# SensorStick.net
KiCad netlist of a schematic drawn in EAGLE
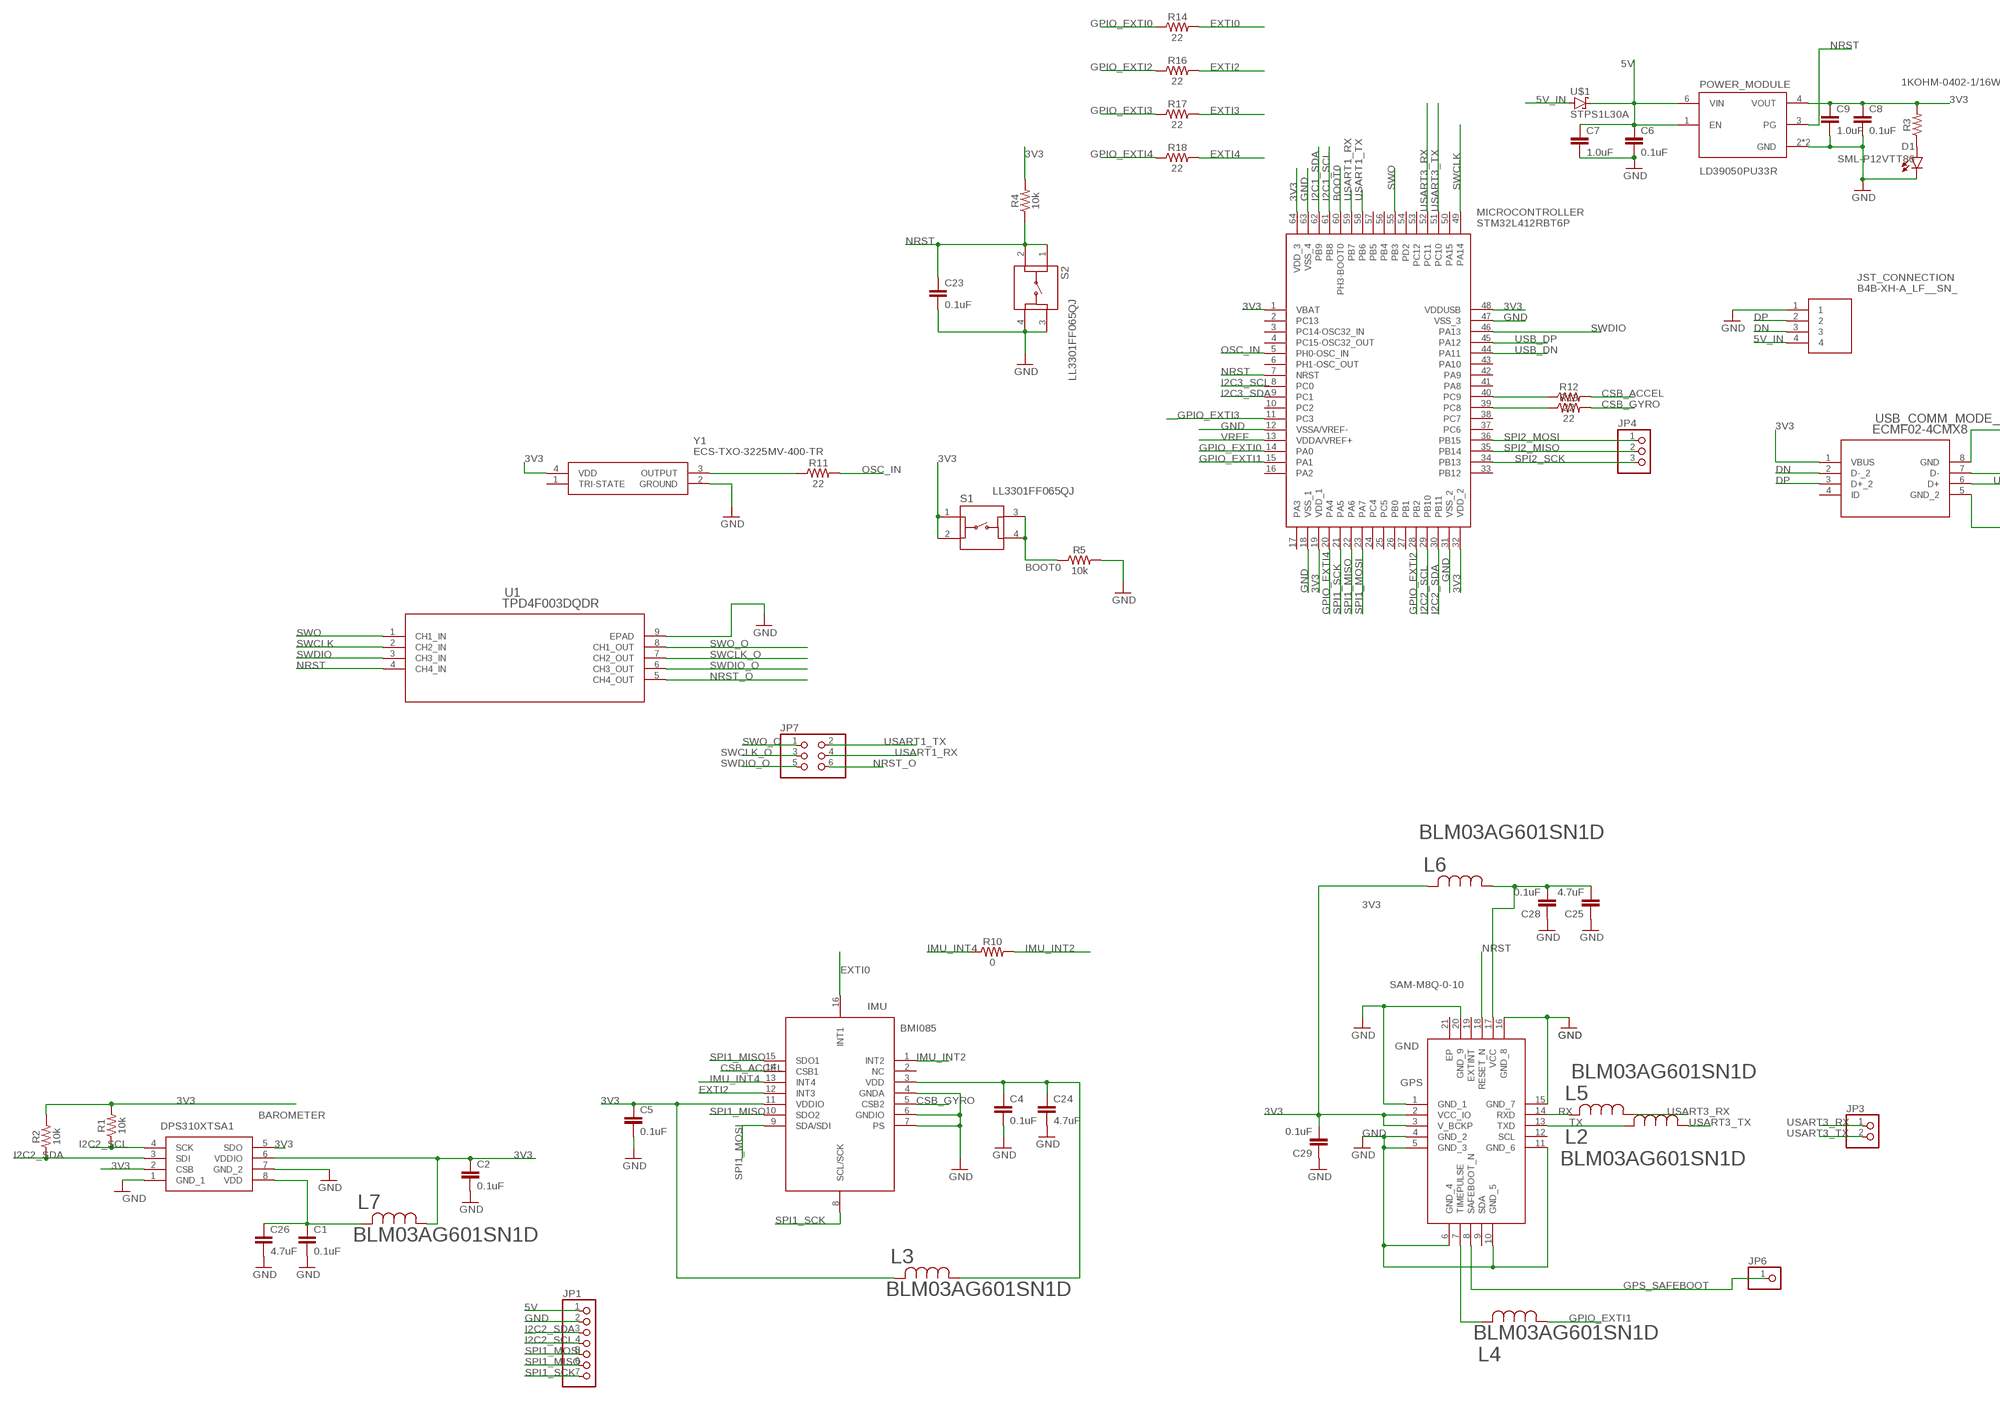
[diagram p0: schematic, sheet 1, part 1 of 2]
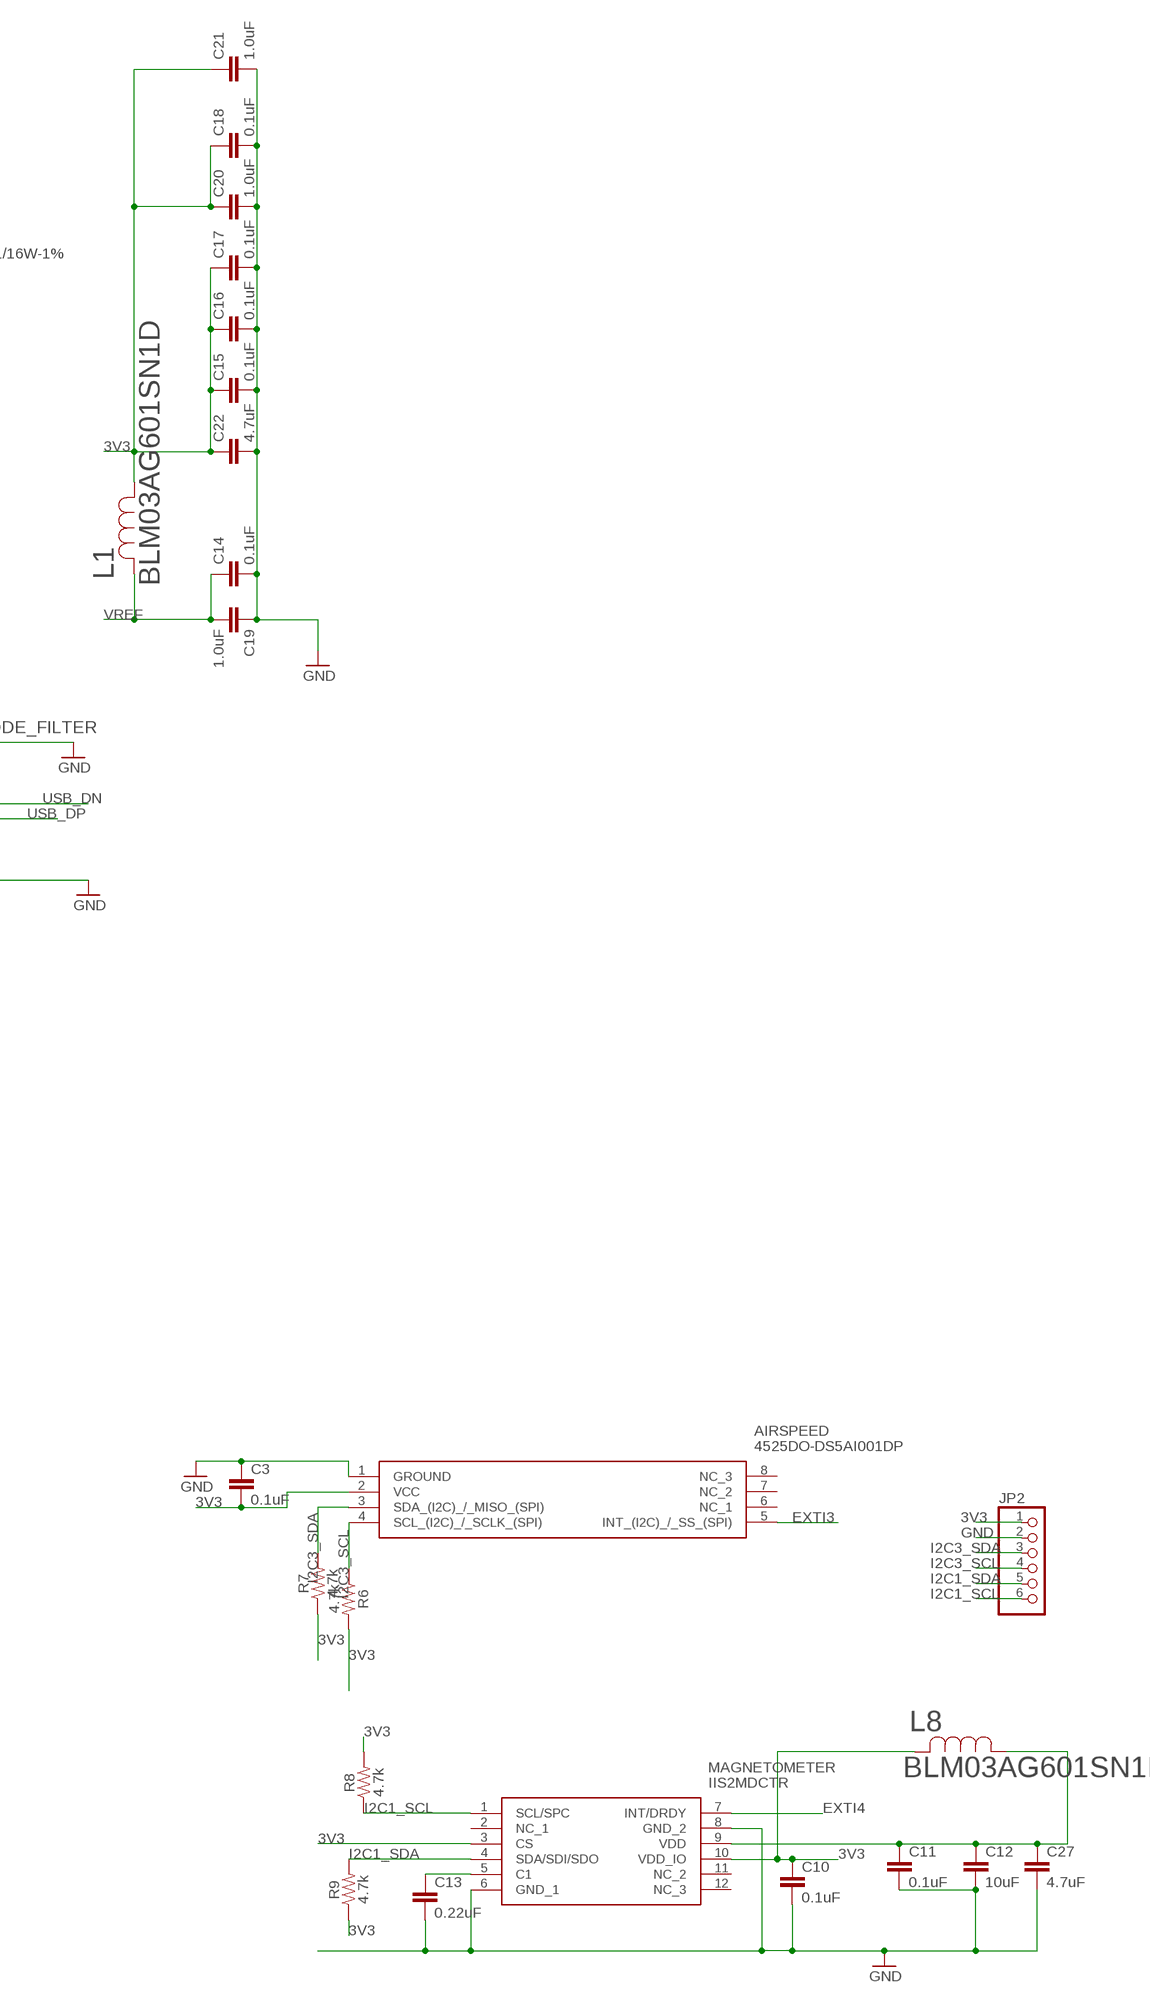
[diagram p1: schematic, sheet 1, part 2 of 2]

(export (version "E")
  (design (tool "Eeschema 10.0.6"))
  (components
    (comp (ref "AIRSPEED")
      (value "4525DO-DS5AI001DP")
      (footprint "eagle-import:4525DO-DS...P")
      (fields (field (name "MOUSER_PART_NUMBER") "824-4525DODS5AI001DP"))
      (libsource (lib "eagle-import") (part "4525DO-DS5AI001DP"))
    )
    (comp (ref "BAROMETER")
      (value "DPS310XTSA1")
      (footprint "eagle-import:DPS310XTSA1")
      (fields (field (name "MOUSER_PART_NUMBER") "726-DPS310XTSA1"))
      (libsource (lib "eagle-import") (part "DPS310XTSA1"))
    )
    (comp (ref "C1")
      (value "0.1uF")
      (footprint "eagle-import:0402")
      (libsource (lib "eagle-import") (part "0.1UF-0402-6.3V-10%-X7R"))
    )
    (comp (ref "C2")
      (value "0.1uF")
      (footprint "eagle-import:0402")
      (libsource (lib "eagle-import") (part "0.1UF-0402-6.3V-10%-X7R"))
    )
    (comp (ref "C3")
      (value "0.1uF")
      (footprint "eagle-import:0402")
      (fields (field (name "SPICEPREFIX") "C"))
      (libsource (lib "eagle-import") (part "0.1UF-0402-6.3V-10%-X7R"))
    )
    (comp (ref "C4")
      (value "0.1uF")
      (footprint "eagle-import:0402")
      (libsource (lib "eagle-import") (part "0.1UF-0402-6.3V-10%-X7R"))
    )
    (comp (ref "C5")
      (value "0.1uF")
      (footprint "eagle-import:0402")
      (libsource (lib "eagle-import") (part "0.1UF-0402-6.3V-10%-X7R"))
    )
    (comp (ref "C6")
      (value "0.1uF")
      (footprint "eagle-import:0402")
      (libsource (lib "eagle-import") (part "0.1UF-0402-6.3V-10%-X7R"))
    )
    (comp (ref "C7")
      (value "1.0uF")
      (footprint "eagle-import:0402")
      (libsource (lib "eagle-import") (part "1.0UF-0402-16V-10%"))
    )
    (comp (ref "C8")
      (value "0.1uF")
      (footprint "eagle-import:0402")
      (libsource (lib "eagle-import") (part "0.1UF-0402-6.3V-10%-X7R"))
    )
    (comp (ref "C9")
      (value "1.0uF")
      (footprint "eagle-import:0402")
      (libsource (lib "eagle-import") (part "1.0UF-0402-16V-10%"))
    )
    (comp (ref "C10")
      (value "0.1uF")
      (footprint "eagle-import:0402")
      (libsource (lib "eagle-import") (part "0.1UF-0402-6.3V-10%-X7R"))
    )
    (comp (ref "C11")
      (value "0.1uF")
      (footprint "eagle-import:0402")
      (libsource (lib "eagle-import") (part "0.1UF-0402-6.3V-10%-X7R"))
    )
    (comp (ref "C12")
      (value "10uF")
      (footprint "eagle-import:0603")
      (libsource (lib "eagle-import") (part "10UF-0603-6.3V-20%"))
    )
    (comp (ref "C13")
      (value "0.22uF")
      (footprint "eagle-import:0603")
      (libsource (lib "eagle-import") (part "0.22UF-0603-25V-10%"))
    )
    (comp (ref "C14")
      (value "0.1uF")
      (footprint "eagle-import:0603")
      (libsource (lib "eagle-import") (part "SparkFun-Capacitors_510_0.1UF-0603-25V-5%"))
    )
    (comp (ref "C15")
      (value "0.1uF")
      (footprint "eagle-import:0603")
      (libsource (lib "eagle-import") (part "SparkFun-Capacitors_510_0.1UF-0603-25V-5%"))
    )
    (comp (ref "C16")
      (value "0.1uF")
      (footprint "eagle-import:0603")
      (libsource (lib "eagle-import") (part "SparkFun-Capacitors_510_0.1UF-0603-25V-5%"))
    )
    (comp (ref "C17")
      (value "0.1uF")
      (footprint "eagle-import:0603")
      (libsource (lib "eagle-import") (part "SparkFun-Capacitors_510_0.1UF-0603-25V-5%"))
    )
    (comp (ref "C18")
      (value "0.1uF")
      (footprint "eagle-import:0603")
      (libsource (lib "eagle-import") (part "SparkFun-Capacitors_510_0.1UF-0603-25V-5%"))
    )
    (comp (ref "C19")
      (value "1.0uF")
      (footprint "eagle-import:0805")
      (libsource (lib "eagle-import") (part "SparkFun-Capacitors_510_1.0UF-0805-25V-10%"))
    )
    (comp (ref "C20")
      (value "1.0uF")
      (footprint "eagle-import:0805")
      (libsource (lib "eagle-import") (part "SparkFun-Capacitors_510_1.0UF-0805-25V-10%"))
    )
    (comp (ref "C21")
      (value "1.0uF")
      (footprint "eagle-import:0805")
      (libsource (lib "eagle-import") (part "SparkFun-Capacitors_510_1.0UF-0805-25V-10%"))
    )
    (comp (ref "C22")
      (value "4.7uF")
      (footprint "eagle-import:0603")
      (libsource (lib "eagle-import") (part "4.7UF0603"))
    )
    (comp (ref "C23")
      (value "0.1uF")
      (footprint "eagle-import:0603")
      (libsource (lib "eagle-import") (part "SparkFun-Capacitors_510_0.1UF-0603-25V-5%"))
    )
    (comp (ref "C24")
      (value "4.7uF")
      (footprint "eagle-import:0603")
      (libsource (lib "eagle-import") (part "4.7UF0603"))
    )
    (comp (ref "C25")
      (value "4.7uF")
      (footprint "eagle-import:0603")
      (libsource (lib "eagle-import") (part "4.7UF0603"))
    )
    (comp (ref "C26")
      (value "4.7uF")
      (footprint "eagle-import:0603")
      (libsource (lib "eagle-import") (part "4.7UF0603"))
    )
    (comp (ref "C27")
      (value "4.7uF")
      (footprint "eagle-import:0603")
      (libsource (lib "eagle-import") (part "4.7UF0603"))
    )
    (comp (ref "C28")
      (value "0.1uF")
      (footprint "eagle-import:0402")
      (libsource (lib "eagle-import") (part "SparkFun-Capacitors_510_0.1UF-0402-16V-10%"))
    )
    (comp (ref "C29")
      (value "0.1uF")
      (footprint "eagle-import:0402")
      (libsource (lib "eagle-import") (part "SparkFun-Capacitors_510_0.1UF-0402-16V-10%"))
    )
    (comp (ref "D1")
      (value "SML-P12VTT86")
      (footprint "eagle-import:LED_SML-P11UTT86R")
      (fields (field (name "MF") "Rohm"))
      (libsource (lib "eagle-import") (part "SML-P12VTT86"))
    )
    (comp (ref "GPS")
      (value "SAM-M8Q-0-10")
      (footprint "eagle-import:SAMM8Q010")
      (libsource (lib "eagle-import") (part "SAM-M8Q-0-10"))
    )
    (comp (ref "IMU")
      (value "BMI085")
      (footprint "eagle-import:BMI085")
      (fields (field (name "MOUSER_PART_NUMBER") "262-BMI085"))
      (libsource (lib "eagle-import") (part "BMI085"))
    )
    (comp (ref "JP1")
      (value "PINHD-1X7")
      (footprint "eagle-import:1X07")
      (libsource (lib "eagle-import") (part "PINHD-1X7"))
    )
    (comp (ref "JP2")
      (value "PINHD-1X6")
      (footprint "eagle-import:1X06")
      (libsource (lib "eagle-import") (part "PINHD-1X6"))
    )
    (comp (ref "JP3")
      (value "PINHD-1X2")
      (footprint "eagle-import:1X02")
      (libsource (lib "eagle-import") (part "PINHD-1X2"))
    )
    (comp (ref "JP4")
      (value "PINHD-1X3")
      (footprint "eagle-import:1X03")
      (libsource (lib "eagle-import") (part "PINHD-1X3"))
    )
    (comp (ref "JP6")
      (value "PINHD-1X1")
      (footprint "eagle-import:1X01")
      (libsource (lib "eagle-import") (part "PINHD-1X1"))
    )
    (comp (ref "JP7")
      (value "PINHD-2X3")
      (footprint "eagle-import:2X03")
      (libsource (lib "eagle-import") (part "PINHD-2X3"))
    )
    (comp (ref "JST_CONNECTION")
      (value "B4B-XH-A_LF__SN_")
      (footprint "eagle-import:B4BXHALFSN")
      (fields (field (name "ARROW_PART_NUMBER") "B4B-XH-A(LF)(SN)"))
      (libsource (lib "eagle-import") (part "B4B-XH-A_LF__SN_"))
    )
    (comp (ref "L1")
      (value "BLM03AG601SN1D")
      (footprint "eagle-import:IND_BLM03_0201_MUR")
      (fields (field (name "COPYRIGHT") "Copyright (C) 2023 Ultra Librarian. All rights reserved."))
      (libsource (lib "eagle-import") (part "BLM03AG601SN1D"))
    )
    (comp (ref "L2")
      (value "BLM03AG601SN1D")
      (footprint "eagle-import:IND_BLM03_0201_MUR")
      (fields (field (name "COPYRIGHT") "Copyright (C) 2023 Ultra Librarian. All rights reserved."))
      (libsource (lib "eagle-import") (part "BLM03AG601SN1D"))
    )
    (comp (ref "L3")
      (value "BLM03AG601SN1D")
      (footprint "eagle-import:IND_BLM03_0201_MUR")
      (fields (field (name "COPYRIGHT") "Copyright (C) 2023 Ultra Librarian. All rights reserved."))
      (libsource (lib "eagle-import") (part "BLM03AG601SN1D"))
    )
    (comp (ref "L4")
      (value "BLM03AG601SN1D")
      (footprint "eagle-import:IND_BLM03_0201_MUR")
      (fields (field (name "COPYRIGHT") "Copyright (C) 2023 Ultra Librarian. All rights reserved."))
      (libsource (lib "eagle-import") (part "BLM03AG601SN1D"))
    )
    (comp (ref "L5")
      (value "BLM03AG601SN1D")
      (footprint "eagle-import:IND_BLM03_0201_MUR")
      (fields (field (name "COPYRIGHT") "Copyright (C) 2023 Ultra Librarian. All rights reserved."))
      (libsource (lib "eagle-import") (part "BLM03AG601SN1D"))
    )
    (comp (ref "L6")
      (value "BLM03AG601SN1D")
      (footprint "eagle-import:IND_BLM03_0201_MUR")
      (fields (field (name "COPYRIGHT") "Copyright (C) 2023 Ultra Librarian. All rights reserved."))
      (libsource (lib "eagle-import") (part "BLM03AG601SN1D"))
    )
    (comp (ref "L7")
      (value "BLM03AG601SN1D")
      (footprint "eagle-import:IND_BLM03_0201_MUR")
      (fields (field (name "COPYRIGHT") "Copyright (C) 2023 Ultra Librarian. All rights reserved."))
      (libsource (lib "eagle-import") (part "BLM03AG601SN1D"))
    )
    (comp (ref "L8")
      (value "BLM03AG601SN1D")
      (footprint "eagle-import:IND_BLM03_0201_MUR")
      (fields (field (name "COPYRIGHT") "Copyright (C) 2023 Ultra Librarian. All rights reserved."))
      (libsource (lib "eagle-import") (part "BLM03AG601SN1D"))
    )
    (comp (ref "MAGNETOMETER")
      (value "IIS2MDCTR")
      (footprint "eagle-import:IIS2MDCTR")
      (fields (field (name "MOUSER_PART_NUMBER") "511-IIS2MDCTR"))
      (libsource (lib "eagle-import") (part "IIS2MDCTR"))
    )
    (comp (ref "MICROCONTROLLER")
      (value "STM32L412RBT6P")
      (footprint "eagle-import:QFP50P1200X1200X160-64N")
      (fields (field (name "MOUSER_PART_NUMBER") "511-STM32L412RBT6P"))
      (libsource (lib "eagle-import") (part "STM32L412RBT6P"))
    )
    (comp (ref "POWER_MODULE")
      (value "LD39050PU33R")
      (footprint "eagle-import:SON95P300X300X100-7N")
      (fields (field (name "MF") "STMicroelectronics"))
      (libsource (lib "eagle-import") (part "LD39050PU33R"))
    )
    (comp (ref "R1")
      (value "10k")
      (footprint "eagle-import:0402")
      (libsource (lib "eagle-import") (part "10KOHM-0402-1/16W-1%"))
    )
    (comp (ref "R2")
      (value "10k")
      (footprint "eagle-import:0402")
      (libsource (lib "eagle-import") (part "10KOHM-0402-1/16W-1%"))
    )
    (comp (ref "R3")
      (value "1KOHM-0402-1/16W-1%")
      (footprint "eagle-import:0402")
      (libsource (lib "eagle-import") (part "1KOHM-0402-1/16W-1%"))
    )
    (comp (ref "R4")
      (value "10k")
      (footprint "eagle-import:0603")
      (libsource (lib "eagle-import") (part "SparkFun-Resistors_532_10KOHM-0603-1/10W-1%"))
    )
    (comp (ref "R5")
      (value "10k")
      (footprint "eagle-import:0603")
      (libsource (lib "eagle-import") (part "SparkFun-Resistors_532_10KOHM-0603-1/10W-1%"))
    )
    (comp (ref "R6")
      (value "4.7k")
      (footprint "eagle-import:0603")
      (libsource (lib "eagle-import") (part "4.7KOHM-0603-1/10W-1%"))
    )
    (comp (ref "R7")
      (value "4.7k")
      (footprint "eagle-import:0603")
      (libsource (lib "eagle-import") (part "4.7KOHM-0603-1/10W-1%"))
    )
    (comp (ref "R8")
      (value "4.7k")
      (footprint "eagle-import:0603")
      (libsource (lib "eagle-import") (part "4.7KOHM-0603-1/10W-1%"))
    )
    (comp (ref "R9")
      (value "4.7k")
      (footprint "eagle-import:0603")
      (libsource (lib "eagle-import") (part "4.7KOHM-0603-1/10W-1%"))
    )
    (comp (ref "R10")
      (value "0")
      (footprint "eagle-import:0603")
      (libsource (lib "eagle-import") (part "0OHM-0603-1/10W-5%"))
    )
    (comp (ref "R11")
      (value "22")
      (footprint "eagle-import:0402")
      (libsource (lib "eagle-import") (part "22OHM-0402-1/10W-1%"))
    )
    (comp (ref "R12")
      (value "22")
      (footprint "eagle-import:0402")
      (libsource (lib "eagle-import") (part "22OHM-0402-1/10W-1%"))
    )
    (comp (ref "R13")
      (value "22")
      (footprint "eagle-import:0402")
      (libsource (lib "eagle-import") (part "22OHM-0402-1/10W-1%"))
    )
    (comp (ref "R14")
      (value "22")
      (footprint "eagle-import:0402")
      (libsource (lib "eagle-import") (part "22OHM-0402-1/10W-1%"))
    )
    (comp (ref "R16")
      (value "22")
      (footprint "eagle-import:0402")
      (libsource (lib "eagle-import") (part "22OHM-0402-1/10W-1%"))
    )
    (comp (ref "R17")
      (value "22")
      (footprint "eagle-import:0402")
      (libsource (lib "eagle-import") (part "22OHM-0402-1/10W-1%"))
    )
    (comp (ref "R18")
      (value "22")
      (footprint "eagle-import:0402")
      (libsource (lib "eagle-import") (part "22OHM-0402-1/10W-1%"))
    )
    (comp (ref "S1")
      (value "LL3301FF065QJ")
      (footprint "eagle-import:LL3301FF065QJ")
      (fields (field (name "MOUSER_PART_NUMBER") "612-LL3301FF065QJ"))
      (libsource (lib "eagle-import") (part "LL3301FF065QJ"))
    )
    (comp (ref "S2")
      (value "LL3301FF065QJ")
      (footprint "eagle-import:LL3301FF065QJ")
      (fields (field (name "MOUSER_PART_NUMBER") "612-LL3301FF065QJ"))
      (libsource (lib "eagle-import") (part "LL3301FF065QJ"))
    )
    (comp (ref "U$1")
      (value "STPS1L30A")
      (footprint "eagle-import:DIOM5226X223N")
      (libsource (lib "eagle-import") (part "STPS1L30A"))
    )
    (comp (ref "U1")
      (value "TPD4F003DQDR")
      (footprint "eagle-import:DQD8_1P2X0P4")
      (fields (field (name "COPYRIGHT") "Copyright (C) 2023 Ultra Librarian. All rights reserved."))
      (libsource (lib "eagle-import") (part "TPD4F003DQDR"))
    )
    (comp (ref "USB_COMM_MODE_FILTER")
      (value "ECMF02-4CMX8")
      (footprint "eagle-import:MICRO_QFN-8L_STM")
      (fields (field (name "COPYRIGHT") "Copyright (C) 2023 Ultra Librarian. All rights reserved."))
      (libsource (lib "eagle-import") (part "ECMF02-4CMX8"))
    )
    (comp (ref "Y1")
      (value "ECS-TXO-3225MV-400-TR")
      (footprint "eagle-import:ECSTXO3225MV400TR")
      (libsource (lib "eagle-import") (part "ECS-TXO-3225MV-400-TR"))
    )
  )
  (nets
    (net (code "1") (name "/3V3") (class "Default")
      (node (ref "AIRSPEED") (pin "2") (pinfunction "VCC_2") (pintype "power_in"))
      (node (ref "BAROMETER") (pin "2") (pinfunction "CSB_2") (pintype "bidirectional"))
      (node (ref "BAROMETER") (pin "5") (pinfunction "SDO_5") (pintype "bidirectional"))
      (node (ref "BAROMETER") (pin "6") (pinfunction "VDDIO_6") (pintype "bidirectional"))
      (node (ref "C10") (pin "1") (pinfunction "1_1") (pintype "passive"))
      (node (ref "C15") (pin "1") (pinfunction "1_1") (pintype "passive"))
      (node (ref "C16") (pin "1") (pinfunction "1_1") (pintype "passive"))
      (node (ref "C17") (pin "1") (pinfunction "1_1") (pintype "passive"))
      (node (ref "C18") (pin "1") (pinfunction "1_1") (pintype "passive"))
      (node (ref "C2") (pin "1") (pinfunction "1_1") (pintype "passive"))
      (node (ref "C20") (pin "1") (pinfunction "1_1") (pintype "passive"))
      (node (ref "C21") (pin "1") (pinfunction "1_1") (pintype "passive"))
      (node (ref "C22") (pin "1") (pinfunction "1_1") (pintype "passive"))
      (node (ref "C29") (pin "2") (pinfunction "2_2") (pintype "passive"))
      (node (ref "C3") (pin "2") (pinfunction "2_2") (pintype "passive"))
      (node (ref "C5") (pin "1") (pinfunction "1_1") (pintype "passive"))
      (node (ref "C8") (pin "1") (pinfunction "1_1") (pintype "passive"))
      (node (ref "C9") (pin "1") (pinfunction "1_1") (pintype "passive"))
      (node (ref "GPS") (pin "2") (pinfunction "VCC_IO_2") (pintype "bidirectional"))
      (node (ref "GPS") (pin "3") (pinfunction "V_BCKP_3") (pintype "bidirectional"))
      (node (ref "IMU") (pin "11") (pinfunction "VDDIO_11") (pintype "bidirectional"))
      (node (ref "JP2") (pin "1") (pinfunction "1_1") (pintype "passive"))
      (node (ref "L1") (pin "1") (pinfunction "1_1") (pintype "passive"))
      (node (ref "L3") (pin "2") (pinfunction "2_2") (pintype "passive"))
      (node (ref "L6") (pin "2") (pinfunction "2_2") (pintype "passive"))
      (node (ref "L7") (pin "1") (pinfunction "1_1") (pintype "passive"))
      (node (ref "L8") (pin "2") (pinfunction "2_2") (pintype "passive"))
      (node (ref "MAGNETOMETER") (pin "10") (pinfunction "VDD_IO_10") (pintype "bidirectional"))
      (node (ref "MAGNETOMETER") (pin "3") (pinfunction "CS_3") (pintype "bidirectional"))
      (node (ref "MICROCONTROLLER") (pin "1") (pinfunction "VBAT_1") (pintype "bidirectional"))
      (node (ref "MICROCONTROLLER") (pin "19") (pinfunction "VDD_1_19") (pintype "bidirectional"))
      (node (ref "MICROCONTROLLER") (pin "32") (pinfunction "VDD_2_32") (pintype "bidirectional"))
      (node (ref "MICROCONTROLLER") (pin "48") (pinfunction "VDDUSB_48") (pintype "bidirectional"))
      (node (ref "MICROCONTROLLER") (pin "64") (pinfunction "VDD_3_64") (pintype "bidirectional"))
      (node (ref "POWER_MODULE") (pin "4") (pinfunction "VOUT_4") (pintype "output"))
      (node (ref "R1") (pin "2") (pinfunction "2_2") (pintype "passive"))
      (node (ref "R2") (pin "2") (pinfunction "2_2") (pintype "passive"))
      (node (ref "R3") (pin "2") (pinfunction "2_2") (pintype "passive"))
      (node (ref "R4") (pin "2") (pinfunction "2_2") (pintype "passive"))
      (node (ref "R6") (pin "2") (pinfunction "2_2") (pintype "passive"))
      (node (ref "R7") (pin "1") (pinfunction "1_1") (pintype "passive"))
      (node (ref "R8") (pin "2") (pinfunction "2_2") (pintype "passive"))
      (node (ref "R9") (pin "1") (pinfunction "1_1") (pintype "passive"))
      (node (ref "S1") (pin "1") (pinfunction "1_1") (pintype "passive"))
      (node (ref "S1") (pin "2") (pinfunction "2_2") (pintype "passive"))
      (node (ref "USB_COMM_MODE_FILTER") (pin "1") (pinfunction "VBUS_1") (pintype "power_in"))
      (node (ref "Y1") (pin "4") (pinfunction "VDD_4") (pintype "bidirectional"))
    )
    (net (code "2") (name "/5V") (class "Default")
      (node (ref "C6") (pin "1") (pinfunction "1_1") (pintype "passive"))
      (node (ref "C7") (pin "1") (pinfunction "1_1") (pintype "passive"))
      (node (ref "JP1") (pin "1") (pinfunction "1_1") (pintype "passive"))
      (node (ref "POWER_MODULE") (pin "1") (pinfunction "EN_1") (pintype "input"))
      (node (ref "POWER_MODULE") (pin "6") (pinfunction "VIN_6") (pintype "power_in"))
      (node (ref "U$1") (pin "1") (pinfunction "C_1") (pintype "passive"))
    )
    (net (code "3") (name "/5V_IN") (class "Default")
      (node (ref "JST_CONNECTION") (pin "4") (pinfunction "4_4") (pintype "bidirectional"))
      (node (ref "U$1") (pin "2") (pinfunction "A_2") (pintype "passive"))
    )
    (net (code "4") (name "/BOOT0") (class "Default")
      (node (ref "MICROCONTROLLER") (pin "60") (pinfunction "PH3-BOOT0_60") (pintype "bidirectional"))
      (node (ref "R5") (pin "1") (pinfunction "1_1") (pintype "passive"))
      (node (ref "S1") (pin "3") (pinfunction "3_3") (pintype "passive"))
      (node (ref "S1") (pin "4") (pinfunction "4_4") (pintype "passive"))
    )
    (net (code "5") (name "/CSB_ACCEL") (class "Default")
      (node (ref "IMU") (pin "14") (pinfunction "CSB1_14") (pintype "bidirectional"))
      (node (ref "R12") (pin "2") (pinfunction "2_2") (pintype "passive"))
    )
    (net (code "6") (name "/CSB_GYRO") (class "Default")
      (node (ref "IMU") (pin "5") (pinfunction "CSB2_5") (pintype "bidirectional"))
      (node (ref "R13") (pin "2") (pinfunction "2_2") (pintype "passive"))
    )
    (net (code "7") (name "/DN") (class "Default")
      (node (ref "JST_CONNECTION") (pin "3") (pinfunction "3_3") (pintype "bidirectional"))
      (node (ref "USB_COMM_MODE_FILTER") (pin "2") (pinfunction "D-_2_2") (pintype "bidirectional"))
    )
    (net (code "8") (name "/DP") (class "Default")
      (node (ref "JST_CONNECTION") (pin "2") (pinfunction "2_2") (pintype "bidirectional"))
      (node (ref "USB_COMM_MODE_FILTER") (pin "3") (pinfunction "D+_2_3") (pintype "bidirectional"))
    )
    (net (code "9") (name "/EXTI0") (class "Default")
      (node (ref "IMU") (pin "16") (pinfunction "INT1_16") (pintype "bidirectional"))
      (node (ref "R14") (pin "2") (pinfunction "2_2") (pintype "passive"))
    )
    (net (code "10") (name "/EXTI2") (class "Default")
      (node (ref "IMU") (pin "12") (pinfunction "INT3_12") (pintype "bidirectional"))
      (node (ref "R16") (pin "2") (pinfunction "2_2") (pintype "passive"))
    )
    (net (code "11") (name "/EXTI3") (class "Default")
      (node (ref "AIRSPEED") (pin "5") (pinfunction "INT_(I2C)_/_SS_(SPI)_5") (pintype "bidirectional"))
      (node (ref "R17") (pin "2") (pinfunction "2_2") (pintype "passive"))
    )
    (net (code "12") (name "/EXTI4") (class "Default")
      (node (ref "MAGNETOMETER") (pin "7") (pinfunction "INT/DRDY_7") (pintype "bidirectional"))
      (node (ref "R18") (pin "2") (pinfunction "2_2") (pintype "passive"))
    )
    (net (code "13") (name "/GPIO_EXTI0") (class "Default")
      (node (ref "MICROCONTROLLER") (pin "14") (pinfunction "PA0_14") (pintype "bidirectional"))
      (node (ref "R14") (pin "1") (pinfunction "1_1") (pintype "passive"))
    )
    (net (code "14") (name "/GPIO_EXTI1") (class "Default")
      (node (ref "L4") (pin "1") (pinfunction "1_1") (pintype "passive"))
      (node (ref "MICROCONTROLLER") (pin "15") (pinfunction "PA1_15") (pintype "bidirectional"))
    )
    (net (code "15") (name "/GPIO_EXTI2") (class "Default")
      (node (ref "MICROCONTROLLER") (pin "28") (pinfunction "PB2_28") (pintype "bidirectional"))
      (node (ref "R16") (pin "1") (pinfunction "1_1") (pintype "passive"))
    )
    (net (code "16") (name "/GPIO_EXTI3") (class "Default")
      (node (ref "MICROCONTROLLER") (pin "11") (pinfunction "PC3_11") (pintype "bidirectional"))
      (node (ref "R17") (pin "1") (pinfunction "1_1") (pintype "passive"))
    )
    (net (code "17") (name "/GPIO_EXTI4") (class "Default")
      (node (ref "MICROCONTROLLER") (pin "20") (pinfunction "PA4_20") (pintype "bidirectional"))
      (node (ref "R18") (pin "1") (pinfunction "1_1") (pintype "passive"))
    )
    (net (code "18") (name "/GPS_SAFEBOOT") (class "Default")
      (node (ref "GPS") (pin "8") (pinfunction "SAFEBOOT_N_8") (pintype "bidirectional"))
      (node (ref "JP6") (pin "1") (pinfunction "1_1") (pintype "passive"))
    )
    (net (code "19") (name "/I2C1_SCL") (class "Default")
      (node (ref "JP2") (pin "6") (pinfunction "6_6") (pintype "passive"))
      (node (ref "MAGNETOMETER") (pin "1") (pinfunction "SCL/SPC_1") (pintype "bidirectional"))
      (node (ref "MICROCONTROLLER") (pin "61") (pinfunction "PB8_61") (pintype "bidirectional"))
      (node (ref "R8") (pin "1") (pinfunction "1_1") (pintype "passive"))
    )
    (net (code "20") (name "/I2C1_SDA") (class "Default")
      (node (ref "JP2") (pin "5") (pinfunction "5_5") (pintype "passive"))
      (node (ref "MAGNETOMETER") (pin "4") (pinfunction "SDA/SDI/SDO_4") (pintype "bidirectional"))
      (node (ref "MICROCONTROLLER") (pin "62") (pinfunction "PB9_62") (pintype "bidirectional"))
      (node (ref "R9") (pin "2") (pinfunction "2_2") (pintype "passive"))
    )
    (net (code "21") (name "/I2C2_SCL") (class "Default")
      (node (ref "BAROMETER") (pin "4") (pinfunction "SCK_4") (pintype "bidirectional"))
      (node (ref "JP1") (pin "4") (pinfunction "4_4") (pintype "passive"))
      (node (ref "MICROCONTROLLER") (pin "29") (pinfunction "PB10_29") (pintype "bidirectional"))
      (node (ref "R1") (pin "1") (pinfunction "1_1") (pintype "passive"))
    )
    (net (code "22") (name "/I2C2_SDA") (class "Default")
      (node (ref "BAROMETER") (pin "3") (pinfunction "SDI_3") (pintype "bidirectional"))
      (node (ref "JP1") (pin "3") (pinfunction "3_3") (pintype "passive"))
      (node (ref "MICROCONTROLLER") (pin "30") (pinfunction "PB11_30") (pintype "bidirectional"))
      (node (ref "R2") (pin "1") (pinfunction "1_1") (pintype "passive"))
    )
    (net (code "23") (name "/I2C3_SCL") (class "Default")
      (node (ref "AIRSPEED") (pin "4") (pinfunction "SCL_(I2C)_/_SCLK_(SPI)_4") (pintype "bidirectional"))
      (node (ref "JP2") (pin "4") (pinfunction "4_4") (pintype "passive"))
      (node (ref "MICROCONTROLLER") (pin "8") (pinfunction "PC0_8") (pintype "bidirectional"))
      (node (ref "R6") (pin "1") (pinfunction "1_1") (pintype "passive"))
    )
    (net (code "24") (name "/I2C3_SDA") (class "Default")
      (node (ref "AIRSPEED") (pin "3") (pinfunction "SDA_(I2C)_/_MISO_(SPI)_3") (pintype "bidirectional"))
      (node (ref "JP2") (pin "3") (pinfunction "3_3") (pintype "passive"))
      (node (ref "MICROCONTROLLER") (pin "9") (pinfunction "PC1_9") (pintype "bidirectional"))
      (node (ref "R7") (pin "2") (pinfunction "2_2") (pintype "passive"))
    )
    (net (code "25") (name "/IMU_INT2") (class "Default")
      (node (ref "IMU") (pin "1") (pinfunction "INT2_1") (pintype "bidirectional"))
      (node (ref "R10") (pin "2") (pinfunction "2_2") (pintype "passive"))
    )
    (net (code "26") (name "/IMU_INT4") (class "Default")
      (node (ref "IMU") (pin "13") (pinfunction "INT4_13") (pintype "bidirectional"))
      (node (ref "R10") (pin "1") (pinfunction "1_1") (pintype "passive"))
    )
    (net (code "27") (name "/NRST") (class "Default")
      (node (ref "C23") (pin "1") (pinfunction "1_1") (pintype "passive"))
      (node (ref "GPS") (pin "18") (pinfunction "RESET_N_18") (pintype "bidirectional"))
      (node (ref "MICROCONTROLLER") (pin "7") (pinfunction "NRST_7") (pintype "bidirectional"))
      (node (ref "POWER_MODULE") (pin "3") (pinfunction "PG_3") (pintype "bidirectional"))
      (node (ref "R4") (pin "1") (pinfunction "1_1") (pintype "passive"))
      (node (ref "S2") (pin "1") (pinfunction "1_1") (pintype "passive"))
      (node (ref "S2") (pin "2") (pinfunction "2_2") (pintype "passive"))
      (node (ref "U1") (pin "4") (pinfunction "CH4_IN_4") (pintype "input"))
    )
    (net (code "28") (name "/NRST_O") (class "Default")
      (node (ref "JP7") (pin "6") (pinfunction "6_6") (pintype "passive"))
      (node (ref "U1") (pin "5") (pinfunction "CH4_OUT_5") (pintype "output"))
    )
    (net (code "29") (name "/OSC_IN") (class "Default")
      (node (ref "MICROCONTROLLER") (pin "5") (pinfunction "PH0-OSC_IN_5") (pintype "bidirectional"))
      (node (ref "R11") (pin "2") (pinfunction "2_2") (pintype "passive"))
    )
    (net (code "30") (name "/RX") (class "Default")
      (node (ref "GPS") (pin "14") (pinfunction "RXD_14") (pintype "bidirectional"))
      (node (ref "L5") (pin "2") (pinfunction "2_2") (pintype "passive"))
    )
    (net (code "31") (name "/SPI1_MISO") (class "Default")
      (node (ref "IMU") (pin "10") (pinfunction "SDO2_10") (pintype "bidirectional"))
      (node (ref "IMU") (pin "15") (pinfunction "SDO1_15") (pintype "bidirectional"))
      (node (ref "JP1") (pin "6") (pinfunction "6_6") (pintype "passive"))
      (node (ref "MICROCONTROLLER") (pin "22") (pinfunction "PA6_22") (pintype "bidirectional"))
    )
    (net (code "32") (name "/SPI1_MOSI") (class "Default")
      (node (ref "IMU") (pin "9") (pinfunction "SDA/SDI_9") (pintype "bidirectional"))
      (node (ref "JP1") (pin "5") (pinfunction "5_5") (pintype "passive"))
      (node (ref "MICROCONTROLLER") (pin "23") (pinfunction "PA7_23") (pintype "bidirectional"))
    )
    (net (code "33") (name "/SPI1_SCK") (class "Default")
      (node (ref "IMU") (pin "8") (pinfunction "SCL/SCK_8") (pintype "bidirectional"))
      (node (ref "JP1") (pin "7") (pinfunction "7_7") (pintype "passive"))
      (node (ref "MICROCONTROLLER") (pin "21") (pinfunction "PA5_21") (pintype "bidirectional"))
    )
    (net (code "34") (name "/SPI2_MISO") (class "Default")
      (node (ref "JP4") (pin "2") (pinfunction "2_2") (pintype "passive"))
      (node (ref "MICROCONTROLLER") (pin "35") (pinfunction "PB14_35") (pintype "bidirectional"))
    )
    (net (code "35") (name "/SPI2_MOSI") (class "Default")
      (node (ref "JP4") (pin "1") (pinfunction "1_1") (pintype "passive"))
      (node (ref "MICROCONTROLLER") (pin "36") (pinfunction "PB15_36") (pintype "bidirectional"))
    )
    (net (code "36") (name "/SPI2_SCK") (class "Default")
      (node (ref "JP4") (pin "3") (pinfunction "3_3") (pintype "passive"))
      (node (ref "MICROCONTROLLER") (pin "34") (pinfunction "PB13_34") (pintype "bidirectional"))
    )
    (net (code "37") (name "/SWCLK") (class "Default")
      (node (ref "MICROCONTROLLER") (pin "49") (pinfunction "PA14_49") (pintype "bidirectional"))
      (node (ref "U1") (pin "2") (pinfunction "CH2_IN_2") (pintype "input"))
    )
    (net (code "38") (name "/SWCLK_O") (class "Default")
      (node (ref "JP7") (pin "3") (pinfunction "3_3") (pintype "passive"))
      (node (ref "U1") (pin "7") (pinfunction "CH2_OUT_7") (pintype "output"))
    )
    (net (code "39") (name "/SWDIO") (class "Default")
      (node (ref "MICROCONTROLLER") (pin "46") (pinfunction "PA13_46") (pintype "bidirectional"))
      (node (ref "U1") (pin "3") (pinfunction "CH3_IN_3") (pintype "input"))
    )
    (net (code "40") (name "/SWDIO_O") (class "Default")
      (node (ref "JP7") (pin "5") (pinfunction "5_5") (pintype "passive"))
      (node (ref "U1") (pin "6") (pinfunction "CH3_OUT_6") (pintype "output"))
    )
    (net (code "41") (name "/SWO") (class "Default")
      (node (ref "MICROCONTROLLER") (pin "55") (pinfunction "PB3_55") (pintype "bidirectional"))
      (node (ref "U1") (pin "1") (pinfunction "CH1_IN_1") (pintype "input"))
    )
    (net (code "42") (name "/SWO_O") (class "Default")
      (node (ref "JP7") (pin "1") (pinfunction "1_1") (pintype "passive"))
      (node (ref "U1") (pin "8") (pinfunction "CH1_OUT_8") (pintype "output"))
    )
    (net (code "43") (name "/TX") (class "Default")
      (node (ref "GPS") (pin "13") (pinfunction "TXD_13") (pintype "bidirectional"))
      (node (ref "L2") (pin "2") (pinfunction "2_2") (pintype "passive"))
    )
    (net (code "44") (name "/USART1_RX") (class "Default")
      (node (ref "JP7") (pin "4") (pinfunction "4_4") (pintype "passive"))
      (node (ref "MICROCONTROLLER") (pin "59") (pinfunction "PB7_59") (pintype "bidirectional"))
    )
    (net (code "45") (name "/USART1_TX") (class "Default")
      (node (ref "JP7") (pin "2") (pinfunction "2_2") (pintype "passive"))
      (node (ref "MICROCONTROLLER") (pin "58") (pinfunction "PB6_58") (pintype "bidirectional"))
    )
    (net (code "46") (name "/USART3_RX") (class "Default")
      (node (ref "JP3") (pin "1") (pinfunction "1_1") (pintype "passive"))
      (node (ref "L5") (pin "1") (pinfunction "1_1") (pintype "passive"))
      (node (ref "MICROCONTROLLER") (pin "52") (pinfunction "PC11_52") (pintype "bidirectional"))
    )
    (net (code "47") (name "/USART3_TX") (class "Default")
      (node (ref "JP3") (pin "2") (pinfunction "2_2") (pintype "passive"))
      (node (ref "L2") (pin "1") (pinfunction "1_1") (pintype "passive"))
      (node (ref "MICROCONTROLLER") (pin "51") (pinfunction "PC10_51") (pintype "bidirectional"))
    )
    (net (code "48") (name "/USB_DN") (class "Default")
      (node (ref "MICROCONTROLLER") (pin "44") (pinfunction "PA11_44") (pintype "bidirectional"))
      (node (ref "USB_COMM_MODE_FILTER") (pin "7") (pinfunction "D-_7") (pintype "bidirectional"))
    )
    (net (code "49") (name "/USB_DP") (class "Default")
      (node (ref "MICROCONTROLLER") (pin "45") (pinfunction "PA12_45") (pintype "bidirectional"))
      (node (ref "USB_COMM_MODE_FILTER") (pin "6") (pinfunction "D+_6") (pintype "bidirectional"))
    )
    (net (code "50") (name "/VREF") (class "Default")
      (node (ref "C14") (pin "1") (pinfunction "1_1") (pintype "passive"))
      (node (ref "C19") (pin "2") (pinfunction "2_2") (pintype "passive"))
      (node (ref "L1") (pin "2") (pinfunction "2_2") (pintype "passive"))
      (node (ref "MICROCONTROLLER") (pin "13") (pinfunction "VDDA/VREF+_13") (pintype "bidirectional"))
    )
    (net (code "51") (name "GND") (class "Default")
      (node (ref "AIRSPEED") (pin "1") (pinfunction "GROUND_1") (pintype "power_in"))
      (node (ref "BAROMETER") (pin "1") (pinfunction "GND_1_1") (pintype "bidirectional"))
      (node (ref "BAROMETER") (pin "7") (pinfunction "GND_2_7") (pintype "bidirectional"))
      (node (ref "C1") (pin "2") (pinfunction "2_2") (pintype "passive"))
      (node (ref "C10") (pin "2") (pinfunction "2_2") (pintype "passive"))
      (node (ref "C11") (pin "2") (pinfunction "2_2") (pintype "passive"))
      (node (ref "C12") (pin "2") (pinfunction "2_2") (pintype "passive"))
      (node (ref "C13") (pin "2") (pinfunction "2_2") (pintype "passive"))
      (node (ref "C14") (pin "2") (pinfunction "2_2") (pintype "passive"))
      (node (ref "C15") (pin "2") (pinfunction "2_2") (pintype "passive"))
      (node (ref "C16") (pin "2") (pinfunction "2_2") (pintype "passive"))
      (node (ref "C17") (pin "2") (pinfunction "2_2") (pintype "passive"))
      (node (ref "C18") (pin "2") (pinfunction "2_2") (pintype "passive"))
      (node (ref "C19") (pin "1") (pinfunction "1_1") (pintype "passive"))
      (node (ref "C2") (pin "2") (pinfunction "2_2") (pintype "passive"))
      (node (ref "C20") (pin "2") (pinfunction "2_2") (pintype "passive"))
      (node (ref "C21") (pin "2") (pinfunction "2_2") (pintype "passive"))
      (node (ref "C22") (pin "2") (pinfunction "2_2") (pintype "passive"))
      (node (ref "C23") (pin "2") (pinfunction "2_2") (pintype "passive"))
      (node (ref "C24") (pin "2") (pinfunction "2_2") (pintype "passive"))
      (node (ref "C25") (pin "1") (pinfunction "1_1") (pintype "passive"))
      (node (ref "C26") (pin "2") (pinfunction "2_2") (pintype "passive"))
      (node (ref "C27") (pin "2") (pinfunction "2_2") (pintype "passive"))
      (node (ref "C28") (pin "1") (pinfunction "1_1") (pintype "passive"))
      (node (ref "C29") (pin "1") (pinfunction "1_1") (pintype "passive"))
      (node (ref "C3") (pin "1") (pinfunction "1_1") (pintype "passive"))
      (node (ref "C4") (pin "2") (pinfunction "2_2") (pintype "passive"))
      (node (ref "C5") (pin "2") (pinfunction "2_2") (pintype "passive"))
      (node (ref "C6") (pin "2") (pinfunction "2_2") (pintype "passive"))
      (node (ref "C7") (pin "2") (pinfunction "2_2") (pintype "passive"))
      (node (ref "C8") (pin "2") (pinfunction "2_2") (pintype "passive"))
      (node (ref "C9") (pin "2") (pinfunction "2_2") (pintype "passive"))
      (node (ref "D1") (pin "C") (pinfunction "C_C") (pintype "passive"))
      (node (ref "GPS") (pin "1") (pinfunction "GND_1_1") (pintype "bidirectional"))
      (node (ref "GPS") (pin "10") (pinfunction "GND_5_10") (pintype "bidirectional"))
      (node (ref "GPS") (pin "11") (pinfunction "GND_6_11") (pintype "bidirectional"))
      (node (ref "GPS") (pin "15") (pinfunction "GND_7_15") (pintype "bidirectional"))
      (node (ref "GPS") (pin "16") (pinfunction "GND_8_16") (pintype "bidirectional"))
      (node (ref "GPS") (pin "20") (pinfunction "GND_9_20") (pintype "bidirectional"))
      (node (ref "GPS") (pin "4") (pinfunction "GND_2_4") (pintype "bidirectional"))
      (node (ref "GPS") (pin "5") (pinfunction "GND_3_5") (pintype "bidirectional"))
      (node (ref "GPS") (pin "6") (pinfunction "GND_4_6") (pintype "bidirectional"))
      (node (ref "IMU") (pin "4") (pinfunction "GNDA_4") (pintype "bidirectional"))
      (node (ref "IMU") (pin "6") (pinfunction "GNDIO_6") (pintype "bidirectional"))
      (node (ref "IMU") (pin "7") (pinfunction "PS_7") (pintype "bidirectional"))
      (node (ref "JP1") (pin "2") (pinfunction "2_2") (pintype "passive"))
      (node (ref "JP2") (pin "2") (pinfunction "2_2") (pintype "passive"))
      (node (ref "JST_CONNECTION") (pin "1") (pinfunction "1_1") (pintype "bidirectional"))
      (node (ref "MAGNETOMETER") (pin "6") (pinfunction "GND_1_6") (pintype "bidirectional"))
      (node (ref "MAGNETOMETER") (pin "8") (pinfunction "GND_2_8") (pintype "bidirectional"))
      (node (ref "MICROCONTROLLER") (pin "12") (pinfunction "VSSA/VREF-_12") (pintype "bidirectional"))
      (node (ref "MICROCONTROLLER") (pin "18") (pinfunction "VSS_1_18") (pintype "bidirectional"))
      (node (ref "MICROCONTROLLER") (pin "31") (pinfunction "VSS_2_31") (pintype "bidirectional"))
      (node (ref "MICROCONTROLLER") (pin "47") (pinfunction "VSS_3_47") (pintype "bidirectional"))
      (node (ref "MICROCONTROLLER") (pin "63") (pinfunction "VSS_4_63") (pintype "bidirectional"))
      (node (ref "POWER_MODULE") (pin "2") (pinfunction "GND_2") (pintype "power_in"))
      (node (ref "POWER_MODULE") (pin "7") (pinfunction "GND_7") (pintype "power_in"))
      (node (ref "R5") (pin "2") (pinfunction "2_2") (pintype "passive"))
      (node (ref "S2") (pin "3") (pinfunction "3_3") (pintype "passive"))
      (node (ref "S2") (pin "4") (pinfunction "4_4") (pintype "passive"))
      (node (ref "U1") (pin "9") (pinfunction "EPAD_9") (pintype "passive"))
      (node (ref "USB_COMM_MODE_FILTER") (pin "5") (pinfunction "GND_2_5") (pintype "passive"))
      (node (ref "USB_COMM_MODE_FILTER") (pin "8") (pinfunction "GND_8") (pintype "passive"))
      (node (ref "Y1") (pin "2") (pinfunction "GROUND_2") (pintype "bidirectional"))
    )
    (net (code "52") (name "Net-(BAROMETER-VDD)") (class "Default")
      (node (ref "BAROMETER") (pin "8") (pinfunction "VDD_8") (pintype "bidirectional"))
      (node (ref "C1") (pin "1") (pinfunction "1_1") (pintype "passive"))
      (node (ref "C26") (pin "1") (pinfunction "1_1") (pintype "passive"))
      (node (ref "L7") (pin "2") (pinfunction "2_2") (pintype "passive"))
    )
    (net (code "53") (name "Net-(D1-PadA)") (class "Default")
      (node (ref "D1") (pin "A") (pinfunction "A_A") (pintype "passive"))
      (node (ref "R3") (pin "1") (pinfunction "1_1") (pintype "passive"))
    )
    (net (code "54") (name "Net-(GPS-TIMEPULSE)") (class "Default")
      (node (ref "GPS") (pin "7") (pinfunction "TIMEPULSE_7") (pintype "bidirectional"))
      (node (ref "L4") (pin "2") (pinfunction "2_2") (pintype "passive"))
    )
    (net (code "55") (name "Net-(GPS-VCC)") (class "Default")
      (node (ref "C25") (pin "2") (pinfunction "2_2") (pintype "passive"))
      (node (ref "C28") (pin "2") (pinfunction "2_2") (pintype "passive"))
      (node (ref "GPS") (pin "17") (pinfunction "VCC_17") (pintype "bidirectional"))
      (node (ref "L6") (pin "1") (pinfunction "1_1") (pintype "passive"))
    )
    (net (code "56") (name "Net-(IMU-VDD)") (class "Default")
      (node (ref "C24") (pin "1") (pinfunction "1_1") (pintype "passive"))
      (node (ref "C4") (pin "1") (pinfunction "1_1") (pintype "passive"))
      (node (ref "IMU") (pin "3") (pinfunction "VDD_3") (pintype "bidirectional"))
      (node (ref "L3") (pin "1") (pinfunction "1_1") (pintype "passive"))
    )
    (net (code "57") (name "Net-(MAGNETOMETER-C1)") (class "Default")
      (node (ref "C13") (pin "1") (pinfunction "1_1") (pintype "passive"))
      (node (ref "MAGNETOMETER") (pin "5") (pinfunction "C1_5") (pintype "bidirectional"))
    )
    (net (code "58") (name "Net-(MAGNETOMETER-VDD)") (class "Default")
      (node (ref "C11") (pin "1") (pinfunction "1_1") (pintype "passive"))
      (node (ref "C12") (pin "1") (pinfunction "1_1") (pintype "passive"))
      (node (ref "C27") (pin "1") (pinfunction "1_1") (pintype "passive"))
      (node (ref "L8") (pin "1") (pinfunction "1_1") (pintype "passive"))
      (node (ref "MAGNETOMETER") (pin "9") (pinfunction "VDD_9") (pintype "bidirectional"))
    )
    (net (code "59") (name "Net-(MICROCONTROLLER-PC8)") (class "Default")
      (node (ref "MICROCONTROLLER") (pin "39") (pinfunction "PC8_39") (pintype "bidirectional"))
      (node (ref "R13") (pin "1") (pinfunction "1_1") (pintype "passive"))
    )
    (net (code "60") (name "Net-(MICROCONTROLLER-PC9)") (class "Default")
      (node (ref "MICROCONTROLLER") (pin "40") (pinfunction "PC9_40") (pintype "bidirectional"))
      (node (ref "R12") (pin "1") (pinfunction "1_1") (pintype "passive"))
    )
    (net (code "61") (name "Net-(Y1-OUTPUT)") (class "Default")
      (node (ref "R11") (pin "1") (pinfunction "1_1") (pintype "passive"))
      (node (ref "Y1") (pin "3") (pinfunction "OUTPUT_3") (pintype "bidirectional"))
    )
    (net (code "62") (name "unconnected-(AIRSPEED-NC_1-Pad6)") (class "Default")
      (node (ref "AIRSPEED") (pin "6") (pinfunction "NC_1_6") (pintype "bidirectional"))
    )
    (net (code "63") (name "unconnected-(AIRSPEED-NC_2-Pad7)") (class "Default")
      (node (ref "AIRSPEED") (pin "7") (pinfunction "NC_2_7") (pintype "bidirectional"))
    )
    (net (code "64") (name "unconnected-(AIRSPEED-NC_3-Pad8)") (class "Default")
      (node (ref "AIRSPEED") (pin "8") (pinfunction "NC_3_8") (pintype "bidirectional"))
    )
    (net (code "65") (name "unconnected-(GPS-EP-Pad21)") (class "Default")
      (node (ref "GPS") (pin "21") (pinfunction "EP_21") (pintype "bidirectional"))
    )
    (net (code "66") (name "unconnected-(GPS-EXTINT-Pad19)") (class "Default")
      (node (ref "GPS") (pin "19") (pinfunction "EXTINT_19") (pintype "bidirectional"))
    )
    (net (code "67") (name "unconnected-(GPS-SCL-Pad12)") (class "Default")
      (node (ref "GPS") (pin "12") (pinfunction "SCL_12") (pintype "bidirectional"))
    )
    (net (code "68") (name "unconnected-(GPS-SDA-Pad9)") (class "Default")
      (node (ref "GPS") (pin "9") (pinfunction "SDA_9") (pintype "bidirectional"))
    )
    (net (code "69") (name "unconnected-(IMU-NC-Pad2)") (class "Default")
      (node (ref "IMU") (pin "2") (pinfunction "NC_2") (pintype "no_connect"))
    )
    (net (code "70") (name "unconnected-(MAGNETOMETER-NC_1-Pad2)") (class "Default")
      (node (ref "MAGNETOMETER") (pin "2") (pinfunction "NC_1_2") (pintype "bidirectional"))
    )
    (net (code "71") (name "unconnected-(MAGNETOMETER-NC_2-Pad11)") (class "Default")
      (node (ref "MAGNETOMETER") (pin "11") (pinfunction "NC_2_11") (pintype "bidirectional"))
    )
    (net (code "72") (name "unconnected-(MAGNETOMETER-NC_3-Pad12)") (class "Default")
      (node (ref "MAGNETOMETER") (pin "12") (pinfunction "NC_3_12") (pintype "bidirectional"))
    )
    (net (code "73") (name "unconnected-(MICROCONTROLLER-PA2-Pad16)") (class "Default")
      (node (ref "MICROCONTROLLER") (pin "16") (pinfunction "PA2_16") (pintype "bidirectional"))
    )
    (net (code "74") (name "unconnected-(MICROCONTROLLER-PA3-Pad17)") (class "Default")
      (node (ref "MICROCONTROLLER") (pin "17") (pinfunction "PA3_17") (pintype "bidirectional"))
    )
    (net (code "75") (name "unconnected-(MICROCONTROLLER-PA8-Pad41)") (class "Default")
      (node (ref "MICROCONTROLLER") (pin "41") (pinfunction "PA8_41") (pintype "bidirectional"))
    )
    (net (code "76") (name "unconnected-(MICROCONTROLLER-PA9-Pad42)") (class "Default")
      (node (ref "MICROCONTROLLER") (pin "42") (pinfunction "PA9_42") (pintype "bidirectional"))
    )
    (net (code "77") (name "unconnected-(MICROCONTROLLER-PA10-Pad43)") (class "Default")
      (node (ref "MICROCONTROLLER") (pin "43") (pinfunction "PA10_43") (pintype "bidirectional"))
    )
    (net (code "78") (name "unconnected-(MICROCONTROLLER-PA15-Pad50)") (class "Default")
      (node (ref "MICROCONTROLLER") (pin "50") (pinfunction "PA15_50") (pintype "bidirectional"))
    )
    (net (code "79") (name "unconnected-(MICROCONTROLLER-PB0-Pad26)") (class "Default")
      (node (ref "MICROCONTROLLER") (pin "26") (pinfunction "PB0_26") (pintype "bidirectional"))
    )
    (net (code "80") (name "unconnected-(MICROCONTROLLER-PB1-Pad27)") (class "Default")
      (node (ref "MICROCONTROLLER") (pin "27") (pinfunction "PB1_27") (pintype "bidirectional"))
    )
    (net (code "81") (name "unconnected-(MICROCONTROLLER-PB4-Pad56)") (class "Default")
      (node (ref "MICROCONTROLLER") (pin "56") (pinfunction "PB4_56") (pintype "bidirectional"))
    )
    (net (code "82") (name "unconnected-(MICROCONTROLLER-PB5-Pad57)") (class "Default")
      (node (ref "MICROCONTROLLER") (pin "57") (pinfunction "PB5_57") (pintype "bidirectional"))
    )
    (net (code "83") (name "unconnected-(MICROCONTROLLER-PB12-Pad33)") (class "Default")
      (node (ref "MICROCONTROLLER") (pin "33") (pinfunction "PB12_33") (pintype "bidirectional"))
    )
    (net (code "84") (name "unconnected-(MICROCONTROLLER-PC2-Pad10)") (class "Default")
      (node (ref "MICROCONTROLLER") (pin "10") (pinfunction "PC2_10") (pintype "bidirectional"))
    )
    (net (code "85") (name "unconnected-(MICROCONTROLLER-PC4-Pad24)") (class "Default")
      (node (ref "MICROCONTROLLER") (pin "24") (pinfunction "PC4_24") (pintype "bidirectional"))
    )
    (net (code "86") (name "unconnected-(MICROCONTROLLER-PC5-Pad25)") (class "Default")
      (node (ref "MICROCONTROLLER") (pin "25") (pinfunction "PC5_25") (pintype "bidirectional"))
    )
    (net (code "87") (name "unconnected-(MICROCONTROLLER-PC6-Pad37)") (class "Default")
      (node (ref "MICROCONTROLLER") (pin "37") (pinfunction "PC6_37") (pintype "bidirectional"))
    )
    (net (code "88") (name "unconnected-(MICROCONTROLLER-PC7-Pad38)") (class "Default")
      (node (ref "MICROCONTROLLER") (pin "38") (pinfunction "PC7_38") (pintype "bidirectional"))
    )
    (net (code "89") (name "unconnected-(MICROCONTROLLER-PC12-Pad53)") (class "Default")
      (node (ref "MICROCONTROLLER") (pin "53") (pinfunction "PC12_53") (pintype "bidirectional"))
    )
    (net (code "90") (name "unconnected-(MICROCONTROLLER-PC13-Pad2)") (class "Default")
      (node (ref "MICROCONTROLLER") (pin "2") (pinfunction "PC13_2") (pintype "bidirectional"))
    )
    (net (code "91") (name "unconnected-(MICROCONTROLLER-PC14-OSC32_IN-Pad3)") (class "Default")
      (node (ref "MICROCONTROLLER") (pin "3") (pinfunction "PC14-OSC32_IN_3") (pintype "bidirectional"))
    )
    (net (code "92") (name "unconnected-(MICROCONTROLLER-PC15-OSC32_OUT-Pad4)") (class "Default")
      (node (ref "MICROCONTROLLER") (pin "4") (pinfunction "PC15-OSC32_OUT_4") (pintype "bidirectional"))
    )
    (net (code "93") (name "unconnected-(MICROCONTROLLER-PD2-Pad54)") (class "Default")
      (node (ref "MICROCONTROLLER") (pin "54") (pinfunction "PD2_54") (pintype "bidirectional"))
    )
    (net (code "94") (name "unconnected-(MICROCONTROLLER-PH1-OSC_OUT-Pad6)") (class "Default")
      (node (ref "MICROCONTROLLER") (pin "6") (pinfunction "PH1-OSC_OUT_6") (pintype "bidirectional"))
    )
    (net (code "95") (name "unconnected-(USB_COMM_MODE_FILTER-ID-Pad4)") (class "Default")
      (node (ref "USB_COMM_MODE_FILTER") (pin "4") (pinfunction "ID_4") (pintype "passive"))
    )
    (net (code "96") (name "unconnected-(Y1-TRI-STATE-Pad1)") (class "Default")
      (node (ref "Y1") (pin "1") (pinfunction "TRI-STATE_1") (pintype "bidirectional"))
    )
  )
)
